# DIY_ST-Link_V21.net
KiCad netlist of a schematic drawn in Altium Designer
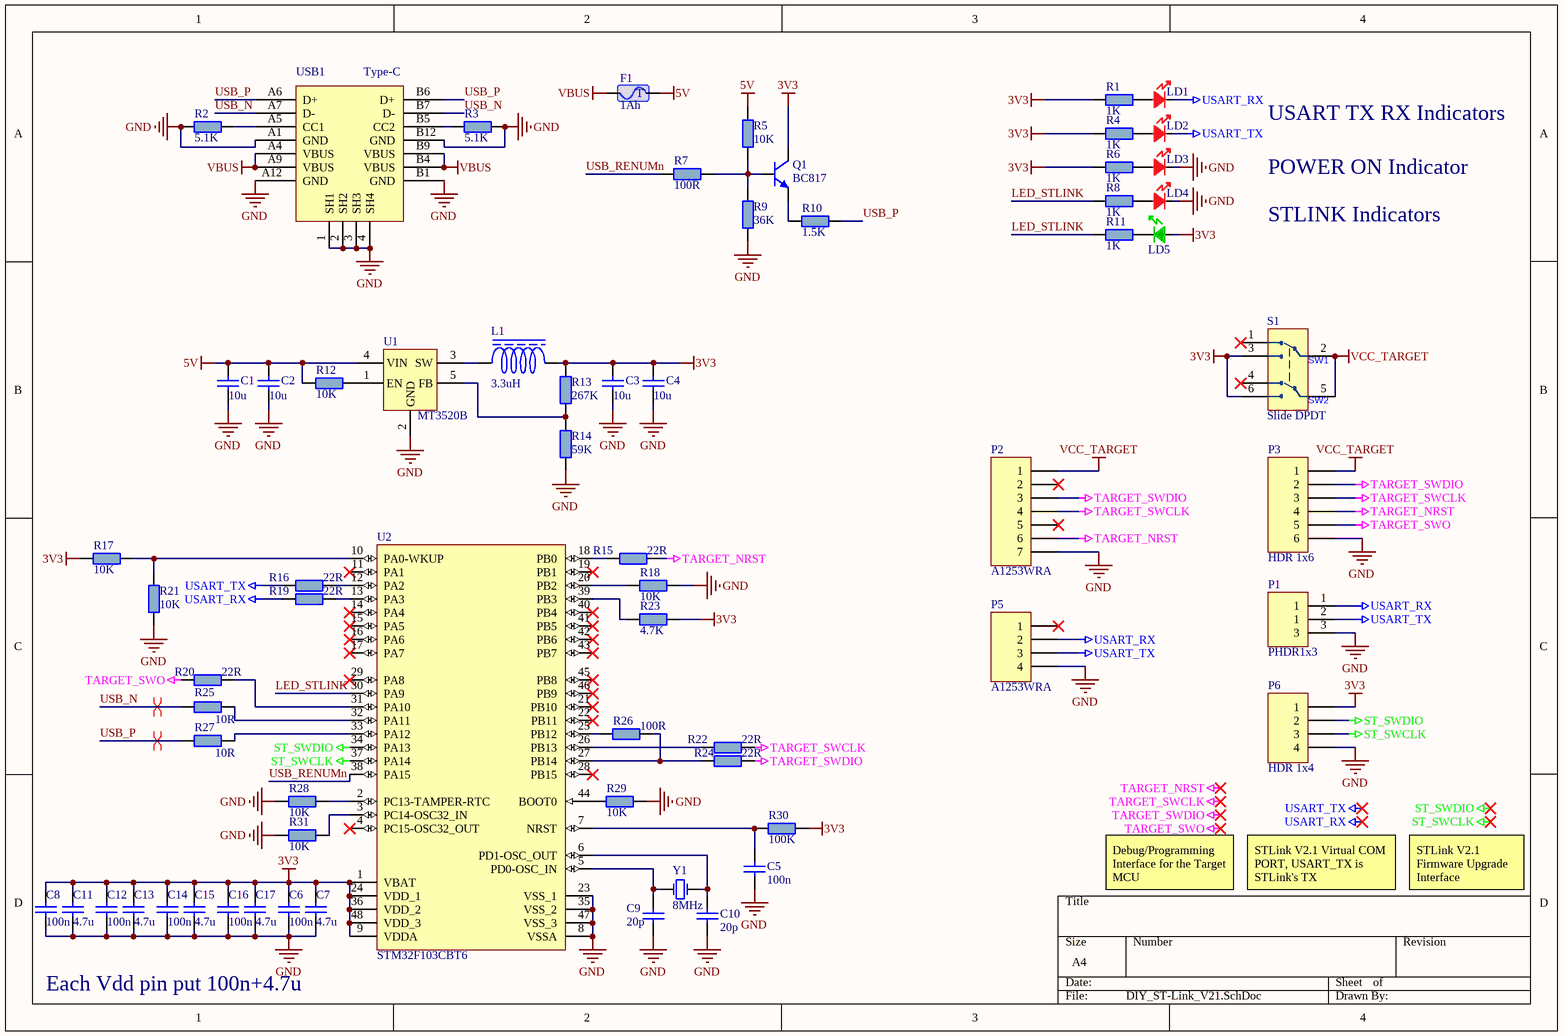
[diagram p0: DIY_ST-Link_V21.SchDoc]

(export (version "E")
  (design (tool "Eeschema 10.0.6"))
  (components
    (comp (ref "C1")
      (value "10u")
      (footprint "0805_CAP")
      (description "Capacitor, Ceramic,, ?F, ?V, 0805")
      (libsource (lib "BC_Schematic Lib SMT") (part "CC_?F_0805"))
    )
    (comp (ref "C2")
      (value "10u")
      (footprint "0805_CAP")
      (description "Capacitor, Ceramic,, ?F, ?V, 0805")
      (libsource (lib "BC_Schematic Lib SMT") (part "CC_?F_0805"))
    )
    (comp (ref "C3")
      (value "10u")
      (footprint "0805_CAP")
      (description "Capacitor, Ceramic,, ?F, ?V, 0805")
      (libsource (lib "BC_Schematic Lib SMT") (part "CC_?F_0805"))
    )
    (comp (ref "C4")
      (value "10u")
      (footprint "0805_CAP")
      (description "Capacitor, Ceramic,, ?F, ?V, 0805")
      (libsource (lib "BC_Schematic Lib SMT") (part "CC_?F_0805"))
    )
    (comp (ref "C5")
      (value "100n")
      (footprint "0805_CAP")
      (description "Capacitor, Ceramic,, ?F, ?V, 0805")
      (libsource (lib "BC_Schematic Lib SMT") (part "CC_?F_0805"))
    )
    (comp (ref "C6")
      (value "100n")
      (footprint "0805_CAP")
      (description "Capacitor, Ceramic,, ?F, ?V, 0805")
      (libsource (lib "BC_Schematic Lib SMT") (part "CC_?F_0805"))
    )
    (comp (ref "C7")
      (value "4.7u")
      (footprint "0805_CAP")
      (description "Capacitor, Ceramic,, ?F, ?V, 0805")
      (libsource (lib "BC_Schematic Lib SMT") (part "CC_?F_0805"))
    )
    (comp (ref "C8")
      (value "100n")
      (footprint "0805_CAP")
      (description "Capacitor, Ceramic,, ?F, ?V, 0805")
      (libsource (lib "BC_Schematic Lib SMT") (part "CC_?F_0805"))
    )
    (comp (ref "C9")
      (value "20p")
      (footprint "0805_CAP")
      (description "Capacitor, Ceramic,, ?F, ?V, 0805")
      (libsource (lib "BC_Schematic Lib SMT") (part "CC_?F_0805"))
    )
    (comp (ref "C10")
      (value "20p")
      (footprint "0805_CAP")
      (description "Capacitor, Ceramic,, ?F, ?V, 0805")
      (libsource (lib "BC_Schematic Lib SMT") (part "CC_?F_0805"))
    )
    (comp (ref "C11")
      (value "4.7u")
      (footprint "0805_CAP")
      (description "Capacitor, Ceramic,, ?F, ?V, 0805")
      (libsource (lib "BC_Schematic Lib SMT") (part "CC_?F_0805"))
    )
    (comp (ref "C12")
      (value "100n")
      (footprint "0805_CAP")
      (description "Capacitor, Ceramic,, ?F, ?V, 0805")
      (libsource (lib "BC_Schematic Lib SMT") (part "CC_?F_0805"))
    )
    (comp (ref "C13")
      (value "4.7u")
      (footprint "0805_CAP")
      (description "Capacitor, Ceramic,, ?F, ?V, 0805")
      (libsource (lib "BC_Schematic Lib SMT") (part "CC_?F_0805"))
    )
    (comp (ref "C14")
      (value "100n")
      (footprint "0805_CAP")
      (description "Capacitor, Ceramic,, ?F, ?V, 0805")
      (libsource (lib "BC_Schematic Lib SMT") (part "CC_?F_0805"))
    )
    (comp (ref "C15")
      (value "4.7u")
      (footprint "0805_CAP")
      (description "Capacitor, Ceramic,, ?F, ?V, 0805")
      (libsource (lib "BC_Schematic Lib SMT") (part "CC_?F_0805"))
    )
    (comp (ref "C16")
      (value "100n")
      (footprint "0805_CAP")
      (description "Capacitor, Ceramic,, ?F, ?V, 0805")
      (libsource (lib "BC_Schematic Lib SMT") (part "CC_?F_0805"))
    )
    (comp (ref "C17")
      (value "4.7u")
      (footprint "0805_CAP")
      (description "Capacitor, Ceramic,, ?F, ?V, 0805")
      (libsource (lib "BC_Schematic Lib SMT") (part "CC_?F_0805"))
    )
    (comp (ref "F1")
      (value "1Ah")
      (footprint "1206_PS")
      (description "Fuse, Polyswitch, 1Ah 1.8At, 6V, 8A @300msec, 210mRmax, 1206 [3216]")
      (libsource (lib "BC_Schematic Lib SMT") (part "Fuse_PS_1A6V_3216"))
    )
    (comp (ref "L1")
      (value "3.3uH")
      (footprint "IND_40x45x3.2")
      (description "https://www.lcsc.com/product-detail/Inductors-SMD_SHOU-HAN-CY43-3-3UH_C2929417.html")
      (libsource (lib "BC_Schematic Lib SMT") (part "IND_?uH_4045"))
    )
    (comp (ref "LD1")
      (value "Red")
      (footprint "LED0805_Red")
      (description "LED, Red, 2.0V, Imax 30mA, 120deg. At 20mA => Wavelength = 630nm, 230mcd, 0805")
      (fields (field (name "MANUFACTURER") "Kingbright"))
      (libsource (lib "BC_Schematic Lib SMT") (part "LED_RED230mcd_2013"))
    )
    (comp (ref "LD2")
      (value "Red")
      (footprint "LED0805_Red")
      (description "LED, Red, 2.0V, Imax 30mA, 120deg. At 20mA => Wavelength = 630nm, 230mcd, 0805")
      (fields (field (name "MANUFACTURER") "Kingbright"))
      (libsource (lib "BC_Schematic Lib SMT") (part "LED_RED230mcd_2013"))
    )
    (comp (ref "LD3")
      (value "Red")
      (footprint "LED0805_Red")
      (description "LED, Red, 2.0V, Imax 30mA, 120deg. At 20mA => Wavelength = 630nm, 230mcd, 0805")
      (fields (field (name "MANUFACTURER") "Kingbright"))
      (libsource (lib "BC_Schematic Lib SMT") (part "LED_RED230mcd_2013"))
    )
    (comp (ref "LD4")
      (value "Red")
      (footprint "LED0805_Red")
      (description "LED, Red, 2.0V, Imax 30mA, 120deg. At 20mA => Wavelength = 630nm, 230mcd, 0805")
      (fields (field (name "MANUFACTURER") "Kingbright"))
      (libsource (lib "BC_Schematic Lib SMT") (part "LED_RED230mcd_2013"))
    )
    (comp (ref "LD5")
      (value "Green")
      (footprint "LED0805_green")
      (description "LED, Green, 2.1V, Imax 30mA, 110deg. At 20mA => Wavelength = 570nm, 50mcd, 0805")
      (fields (field (name "MANUFACTURER") "Kingbright"))
      (libsource (lib "BC_Schematic Lib SMT") (part "LED_GRN50mcd_2013"))
    )
    (comp (ref "P1")
      (value "PHDR1x3")
      (footprint "HEADER_1x3")
      (description "Header, 3 pin SIL, 2.54 pitch")
      (libsource (lib "BC_Schematic Lib") (part "Header1x3"))
    )
    (comp (ref "P2")
      (value "A1253WRA")
      (footprint "A1253WRA-7P")
      (description "A1253WRA-4P")
      (fields (field (name "ENGINEER’S NAME") "WZ"))
      (libsource (lib "BC_Schematic Lib SMT") (part "A1253WRA-7P"))
    )
    (comp (ref "P3")
      (value "HDR 1x6")
      (footprint "HEADER_1x6")
      (description "Header_1x6")
      (libsource (lib "BC_Schematic Lib") (part "Header1x6"))
    )
    (comp (ref "P5")
      (value "A1253WRA")
      (footprint "A1253WRA-4P")
      (description "A1253WRA-4P")
      (fields (field (name "ENGINEER’S NAME") "WZ"))
      (libsource (lib "BC_Schematic Lib SMT") (part "A1253WRA-4P"))
    )
    (comp (ref "P6")
      (value "HDR 1x4")
      (footprint "HEADER_1x4")
      (description "Header_1x4")
      (fields (field (name "ENGINEER’S NAME") "WZ"))
      (libsource (lib "BC_Schematic Lib") (part "Header1x4"))
    )
    (comp (ref "Q1")
      (value "BC817")
      (footprint "SOT23")
      (description "TRANSISTOR, NPN, SOT-23, 45V")
      (fields (field (name "MANUFACTURER") "NXP"))
      (libsource (lib "BC_Schematic Lib SMT") (part "TR_BC817"))
    )
    (comp (ref "R1")
      (value "1K")
      (footprint "0805_res")
      (description "Resistor, ?ohm, 0805")
      (libsource (lib "BC_Schematic Lib SMT") (part "RS_?R_0805"))
    )
    (comp (ref "R2")
      (value "5.1K")
      (footprint "0805_res")
      (description "Resistor, ?ohm, 0805")
      (libsource (lib "") (part "RS_?R_0805_2"))
    )
    (comp (ref "R3")
      (value "5.1K")
      (footprint "0805_res")
      (description "Resistor, ?ohm, 0805")
      (libsource (lib "BC_Schematic Lib SMT") (part "RS_?R_0805"))
    )
    (comp (ref "R4")
      (value "1K")
      (footprint "0805_res")
      (description "Resistor, ?ohm, 0805")
      (libsource (lib "BC_Schematic Lib SMT") (part "RS_?R_0805"))
    )
    (comp (ref "R5")
      (value "10K")
      (footprint "0805_res")
      (description "Resistor, ?ohm, 0805")
      (libsource (lib "") (part "RS_?R_0805_1"))
    )
    (comp (ref "R6")
      (value "1K")
      (footprint "0805_res")
      (description "Resistor, ?ohm, 0805")
      (libsource (lib "BC_Schematic Lib SMT") (part "RS_?R_0805"))
    )
    (comp (ref "R7")
      (value "100R")
      (footprint "0805_res")
      (description "Resistor, ?ohm, 0805")
      (libsource (lib "") (part "RS_?R_0805_2"))
    )
    (comp (ref "R8")
      (value "1K")
      (footprint "0805_res")
      (description "Resistor, ?ohm, 0805")
      (libsource (lib "BC_Schematic Lib SMT") (part "RS_?R_0805"))
    )
    (comp (ref "R9")
      (value "36K")
      (footprint "0805_res")
      (description "Resistor, ?ohm, 0805")
      (libsource (lib "") (part "RS_?R_0805_1"))
    )
    (comp (ref "R10")
      (value "1.5K")
      (footprint "0805_res")
      (description "Resistor, ?ohm, 0805")
      (libsource (lib "") (part "RS_?R_0805_2"))
    )
    (comp (ref "R11")
      (value "1K")
      (footprint "0805_res")
      (description "Resistor, ?ohm, 0805")
      (libsource (lib "BC_Schematic Lib SMT") (part "RS_?R_0805"))
    )
    (comp (ref "R12")
      (value "10K")
      (footprint "0805_res")
      (description "Resistor, ?ohm, 0805")
      (libsource (lib "BC_Schematic Lib SMT") (part "RS_?R_0805"))
    )
    (comp (ref "R13")
      (value "267K")
      (footprint "0805_res")
      (description "Resistor, ?ohm, 0805")
      (libsource (lib "") (part "RS_?R_0805_3"))
    )
    (comp (ref "R14")
      (value "59K")
      (footprint "0805_res")
      (description "Resistor, ?ohm, 0805")
      (libsource (lib "") (part "RS_?R_0805_3"))
    )
    (comp (ref "R15")
      (value "22R")
      (footprint "0805_res")
      (description "Resistor, ?ohm, 0805")
      (libsource (lib "BC_Schematic Lib SMT") (part "RS_?R_0805"))
    )
    (comp (ref "R16")
      (value "22R")
      (footprint "0805_res")
      (description "Resistor, ?ohm, 0805")
      (libsource (lib "BC_Schematic Lib SMT") (part "RS_?R_0805"))
    )
    (comp (ref "R17")
      (value "10K")
      (footprint "0805_res")
      (description "Resistor, ?ohm, 0805")
      (libsource (lib "BC_Schematic Lib SMT") (part "RS_?R_0805"))
    )
    (comp (ref "R18")
      (value "10K")
      (footprint "0805_res")
      (description "Resistor, ?ohm, 0805")
      (libsource (lib "BC_Schematic Lib SMT") (part "RS_?R_0805"))
    )
    (comp (ref "R19")
      (value "22R")
      (footprint "0805_res")
      (description "Resistor, ?ohm, 0805")
      (libsource (lib "BC_Schematic Lib SMT") (part "RS_?R_0805"))
    )
    (comp (ref "R20")
      (value "22R")
      (footprint "0805_res")
      (description "Resistor, ?ohm, 0805")
      (libsource (lib "BC_Schematic Lib SMT") (part "RS_?R_0805"))
    )
    (comp (ref "R21")
      (value "10K")
      (footprint "0805_res")
      (description "Resistor, ?ohm, 0805")
      (libsource (lib "") (part "RS_?R_0805_1"))
    )
    (comp (ref "R22")
      (value "22R")
      (footprint "0805_res")
      (description "Resistor, ?ohm, 0805")
      (libsource (lib "BC_Schematic Lib SMT") (part "RS_?R_0805"))
    )
    (comp (ref "R23")
      (value "4.7K")
      (footprint "0805_res")
      (description "Resistor, ?ohm, 0805")
      (libsource (lib "BC_Schematic Lib SMT") (part "RS_?R_0805"))
    )
    (comp (ref "R24")
      (value "22R")
      (footprint "0805_res")
      (description "Resistor, ?ohm, 0805")
      (libsource (lib "BC_Schematic Lib SMT") (part "RS_?R_0805"))
    )
    (comp (ref "R25")
      (value "10R")
      (footprint "0805_res")
      (description "Resistor, ?ohm, 0805")
      (libsource (lib "BC_Schematic Lib SMT") (part "RS_?R_0805"))
    )
    (comp (ref "R26")
      (value "100R")
      (footprint "0805_res")
      (description "Resistor, ?ohm, 0805")
      (libsource (lib "BC_Schematic Lib SMT") (part "RS_?R_0805"))
    )
    (comp (ref "R27")
      (value "10R")
      (footprint "0805_res")
      (description "Resistor, ?ohm, 0805")
      (libsource (lib "BC_Schematic Lib SMT") (part "RS_?R_0805"))
    )
    (comp (ref "R28")
      (value "10K")
      (footprint "0805_res")
      (description "Resistor, ?ohm, 0805")
      (libsource (lib "BC_Schematic Lib SMT") (part "RS_?R_0805"))
    )
    (comp (ref "R29")
      (value "10K")
      (footprint "0805_res")
      (description "Resistor, ?ohm, 0805")
      (libsource (lib "BC_Schematic Lib SMT") (part "RS_?R_0805"))
    )
    (comp (ref "R30")
      (value "100K")
      (footprint "0805_res")
      (description "Resistor, ?ohm, 0805")
      (libsource (lib "BC_Schematic Lib SMT") (part "RS_?R_0805"))
    )
    (comp (ref "R31")
      (value "10K")
      (footprint "0805_res")
      (description "Resistor, ?ohm, 0805")
      (libsource (lib "BC_Schematic Lib SMT") (part "RS_?R_0805"))
    )
    (comp (ref "S1")
      (value "Slide DPDT")
      (footprint "SW_DPDT_SMD")
      (libsource (lib "BC_Schematic Lib SMT") (part "SW_Slide_DPDT"))
    )
    (comp (ref "U1")
      (value "MT3520B")
      (footprint "SOT23-5")
      (description "https://www.lcsc.com/product-detail/DC-DC-Converters_XI-AN-Aerosemi-Tech-MT3520B_C2684933.html")
      (libsource (lib "BC_Schematic Lib SMT") (part "BUCK_MT3520B"))
    )
    (comp (ref "U2")
      (value "STM32F103CBT6")
      (footprint "LQFP-48")
      (libsource (lib "BC_Schematic Lib SMT") (part "STM32F103CBT6"))
    )
    (comp (ref "USB1")
      (value "Type-C")
      (footprint "Type-C-TOP")
      (libsource (lib "BC_Schematic Lib SMT") (part "USB-Type-C-TOP"))
    )
    (comp (ref "Y1")
      (value "8MHz")
      (footprint "Xtal_HC49_US")
      (description "Crystal, SMD, HC49 Size")
      (fields (field (name "MANUFACTURER") "Abracon Corporation"))
      (libsource (lib "BC_Schematic Lib SMT") (part "XTAL-SMD_HC49"))
    )
  )
  (nets
    (net (code "1") (name "/LED_STLINK") (class "Default")
      (node (ref "R11") (pin "2") (pinfunction "2_2") (pintype "passive"))
      (node (ref "R8") (pin "2") (pinfunction "2_2") (pintype "passive"))
      (node (ref "U2") (pin "30") (pinfunction "PA9_30") (pintype "bidirectional"))
    )
    (net (code "2") (name "/USB_N") (class "Default")
      (node (ref "R25") (pin "2") (pinfunction "2_2") (pintype "passive"))
      (node (ref "USB1") (pin "A7") (pinfunction "D-_A7") (pintype "passive"))
      (node (ref "USB1") (pin "B7") (pinfunction "D-_B7") (pintype "passive"))
    )
    (net (code "3") (name "/USB_P") (class "Default")
      (node (ref "R10") (pin "2") (pinfunction "2_2") (pintype "passive"))
      (node (ref "R27") (pin "2") (pinfunction "2_2") (pintype "passive"))
      (node (ref "USB1") (pin "A6") (pinfunction "D+_A6") (pintype "passive"))
      (node (ref "USB1") (pin "B6") (pinfunction "D+_B6") (pintype "passive"))
    )
    (net (code "4") (name "/USB_RENUMn") (class "Default")
      (node (ref "R7") (pin "1") (pinfunction "1_1") (pintype "passive"))
      (node (ref "U2") (pin "38") (pinfunction "PA15_38") (pintype "bidirectional"))
    )
    (net (code "5") (name "3V3") (class "Default")
      (node (ref "C11") (pin "2") (pinfunction "2_2") (pintype "passive"))
      (node (ref "C12") (pin "2") (pinfunction "2_2") (pintype "passive"))
      (node (ref "C13") (pin "2") (pinfunction "2_2") (pintype "passive"))
      (node (ref "C14") (pin "2") (pinfunction "2_2") (pintype "passive"))
      (node (ref "C15") (pin "2") (pinfunction "2_2") (pintype "passive"))
      (node (ref "C16") (pin "2") (pinfunction "2_2") (pintype "passive"))
      (node (ref "C17") (pin "2") (pinfunction "2_2") (pintype "passive"))
      (node (ref "C3") (pin "2") (pinfunction "2_2") (pintype "passive"))
      (node (ref "C4") (pin "2") (pinfunction "2_2") (pintype "passive"))
      (node (ref "C6") (pin "2") (pinfunction "2_2") (pintype "passive"))
      (node (ref "C7") (pin "2") (pinfunction "2_2") (pintype "passive"))
      (node (ref "C8") (pin "2") (pinfunction "2_2") (pintype "passive"))
      (node (ref "L1") (pin "2") (pinfunction "2_2") (pintype "passive"))
      (node (ref "LD5") (pin "1") (pinfunction "A_1") (pintype "passive"))
      (node (ref "P6") (pin "1") (pinfunction "1_1") (pintype "passive"))
      (node (ref "Q1") (pin "3") (pinfunction "C_3") (pintype "passive"))
      (node (ref "R1") (pin "2") (pinfunction "2_2") (pintype "passive"))
      (node (ref "R13") (pin "1") (pinfunction "1_1") (pintype "passive"))
      (node (ref "R17") (pin "2") (pinfunction "2_2") (pintype "passive"))
      (node (ref "R23") (pin "1") (pinfunction "1_1") (pintype "passive"))
      (node (ref "R30") (pin "1") (pinfunction "1_1") (pintype "passive"))
      (node (ref "R4") (pin "2") (pinfunction "2_2") (pintype "passive"))
      (node (ref "R6") (pin "2") (pinfunction "2_2") (pintype "passive"))
      (node (ref "S1") (pin "3") (pinfunction "NO1_3") (pintype "passive"))
      (node (ref "S1") (pin "6") (pinfunction "NO2_6") (pintype "passive"))
      (node (ref "U2") (pin "1") (pinfunction "VBAT_1") (pintype "power_in"))
      (node (ref "U2") (pin "24") (pinfunction "VDD_1_24") (pintype "power_in"))
      (node (ref "U2") (pin "36") (pinfunction "VDD_2_36") (pintype "power_in"))
      (node (ref "U2") (pin "48") (pinfunction "VDD_3_48") (pintype "power_in"))
      (node (ref "U2") (pin "9") (pinfunction "VDDA_9") (pintype "power_in"))
    )
    (net (code "6") (name "5V") (class "Default")
      (node (ref "C1") (pin "2") (pinfunction "2_2") (pintype "passive"))
      (node (ref "C2") (pin "2") (pinfunction "2_2") (pintype "passive"))
      (node (ref "F1") (pin "2") (pinfunction "2_2") (pintype "passive"))
      (node (ref "R12") (pin "2") (pinfunction "2_2") (pintype "passive"))
      (node (ref "R5") (pin "2") (pinfunction "2_2") (pintype "passive"))
      (node (ref "U1") (pin "4") (pinfunction "VIN_4") (pintype "passive"))
    )
    (net (code "7") (name "GND") (class "Default")
      (node (ref "C1") (pin "1") (pinfunction "1_1") (pintype "passive"))
      (node (ref "C10") (pin "1") (pinfunction "1_1") (pintype "passive"))
      (node (ref "C11") (pin "1") (pinfunction "1_1") (pintype "passive"))
      (node (ref "C12") (pin "1") (pinfunction "1_1") (pintype "passive"))
      (node (ref "C13") (pin "1") (pinfunction "1_1") (pintype "passive"))
      (node (ref "C14") (pin "1") (pinfunction "1_1") (pintype "passive"))
      (node (ref "C15") (pin "1") (pinfunction "1_1") (pintype "passive"))
      (node (ref "C16") (pin "1") (pinfunction "1_1") (pintype "passive"))
      (node (ref "C17") (pin "1") (pinfunction "1_1") (pintype "passive"))
      (node (ref "C2") (pin "1") (pinfunction "1_1") (pintype "passive"))
      (node (ref "C3") (pin "1") (pinfunction "1_1") (pintype "passive"))
      (node (ref "C4") (pin "1") (pinfunction "1_1") (pintype "passive"))
      (node (ref "C5") (pin "1") (pinfunction "1_1") (pintype "passive"))
      (node (ref "C6") (pin "1") (pinfunction "1_1") (pintype "passive"))
      (node (ref "C7") (pin "1") (pinfunction "1_1") (pintype "passive"))
      (node (ref "C8") (pin "1") (pinfunction "1_1") (pintype "passive"))
      (node (ref "C9") (pin "1") (pinfunction "1_1") (pintype "passive"))
      (node (ref "LD3") (pin "2") (pinfunction "K_2") (pintype "passive"))
      (node (ref "LD4") (pin "2") (pinfunction "K_2") (pintype "passive"))
      (node (ref "P1") (pin "3") (pinfunction "3_3") (pintype "passive"))
      (node (ref "P2") (pin "7") (pinfunction "7_7") (pintype "passive"))
      (node (ref "P3") (pin "6") (pinfunction "6_6") (pintype "passive"))
      (node (ref "P5") (pin "4") (pinfunction "4_4") (pintype "passive"))
      (node (ref "P6") (pin "4") (pinfunction "4_4") (pintype "passive"))
      (node (ref "R14") (pin "2") (pinfunction "2_2") (pintype "passive"))
      (node (ref "R18") (pin "1") (pinfunction "1_1") (pintype "passive"))
      (node (ref "R2") (pin "1") (pinfunction "1_1") (pintype "passive"))
      (node (ref "R21") (pin "1") (pinfunction "1_1") (pintype "passive"))
      (node (ref "R28") (pin "2") (pinfunction "2_2") (pintype "passive"))
      (node (ref "R29") (pin "1") (pinfunction "1_1") (pintype "passive"))
      (node (ref "R3") (pin "1") (pinfunction "1_1") (pintype "passive"))
      (node (ref "R31") (pin "2") (pinfunction "2_2") (pintype "passive"))
      (node (ref "R9") (pin "1") (pinfunction "1_1") (pintype "passive"))
      (node (ref "U1") (pin "2") (pinfunction "GND_2") (pintype "passive"))
      (node (ref "U2") (pin "23") (pinfunction "VSS_1_23") (pintype "power_in"))
      (node (ref "U2") (pin "35") (pinfunction "VSS_2_35") (pintype "power_in"))
      (node (ref "U2") (pin "47") (pinfunction "VSS_3_47") (pintype "power_in"))
      (node (ref "U2") (pin "8") (pinfunction "VSSA_8") (pintype "power_in"))
      (node (ref "USB1") (pin "1") (pinfunction "SH1_1") (pintype "passive"))
      (node (ref "USB1") (pin "2") (pinfunction "SH2_2") (pintype "passive"))
      (node (ref "USB1") (pin "3") (pinfunction "SH3_3") (pintype "passive"))
      (node (ref "USB1") (pin "4") (pinfunction "SH4_4") (pintype "passive"))
      (node (ref "USB1") (pin "A1") (pinfunction "GND_A1") (pintype "passive"))
      (node (ref "USB1") (pin "A12") (pinfunction "GND_A12") (pintype "passive"))
      (node (ref "USB1") (pin "B1") (pinfunction "GND_B1") (pintype "passive"))
      (node (ref "USB1") (pin "B12") (pinfunction "GND_B12") (pintype "passive"))
    )
    (net (code "8") (name "Net-(LD1-A)") (class "Default")
      (node (ref "LD1") (pin "1") (pinfunction "A_1") (pintype "passive"))
      (node (ref "R1") (pin "1") (pinfunction "1_1") (pintype "passive"))
    )
    (net (code "9") (name "Net-(LD2-A)") (class "Default")
      (node (ref "LD2") (pin "1") (pinfunction "A_1") (pintype "passive"))
      (node (ref "R4") (pin "1") (pinfunction "1_1") (pintype "passive"))
    )
    (net (code "10") (name "Net-(LD3-A)") (class "Default")
      (node (ref "LD3") (pin "1") (pinfunction "A_1") (pintype "passive"))
      (node (ref "R6") (pin "1") (pinfunction "1_1") (pintype "passive"))
    )
    (net (code "11") (name "Net-(LD4-A)") (class "Default")
      (node (ref "LD4") (pin "1") (pinfunction "A_1") (pintype "passive"))
      (node (ref "R8") (pin "1") (pinfunction "1_1") (pintype "passive"))
    )
    (net (code "12") (name "Net-(LD5-K)") (class "Default")
      (node (ref "LD5") (pin "2") (pinfunction "K_2") (pintype "passive"))
      (node (ref "R11") (pin "1") (pinfunction "1_1") (pintype "passive"))
    )
    (net (code "13") (name "Net-(Q1-B)") (class "Default")
      (node (ref "Q1") (pin "1") (pinfunction "B_1") (pintype "passive"))
      (node (ref "R5") (pin "1") (pinfunction "1_1") (pintype "passive"))
      (node (ref "R7") (pin "2") (pinfunction "2_2") (pintype "passive"))
      (node (ref "R9") (pin "2") (pinfunction "2_2") (pintype "passive"))
    )
    (net (code "14") (name "Net-(Q1-E)") (class "Default")
      (node (ref "Q1") (pin "2") (pinfunction "E_2") (pintype "passive"))
      (node (ref "R10") (pin "1") (pinfunction "1_1") (pintype "passive"))
    )
    (net (code "15") (name "Net-(U1-EN)") (class "Default")
      (node (ref "R12") (pin "1") (pinfunction "1_1") (pintype "passive"))
      (node (ref "U1") (pin "1") (pinfunction "EN_1") (pintype "passive"))
    )
    (net (code "16") (name "Net-(U1-FB)") (class "Default")
      (node (ref "R13") (pin "2") (pinfunction "2_2") (pintype "passive"))
      (node (ref "R14") (pin "1") (pinfunction "1_1") (pintype "passive"))
      (node (ref "U1") (pin "5") (pinfunction "FB_5") (pintype "passive"))
    )
    (net (code "17") (name "Net-(U1-SW)") (class "Default")
      (node (ref "L1") (pin "1") (pinfunction "1_1") (pintype "passive"))
      (node (ref "U1") (pin "3") (pinfunction "SW_3") (pintype "passive"))
    )
    (net (code "18") (name "Net-(U2-BOOT0)") (class "Default")
      (node (ref "R29") (pin "2") (pinfunction "2_2") (pintype "passive"))
      (node (ref "U2") (pin "44") (pinfunction "BOOT0_44") (pintype "input"))
    )
    (net (code "19") (name "Net-(U2-NRST)") (class "Default")
      (node (ref "C5") (pin "2") (pinfunction "2_2") (pintype "passive"))
      (node (ref "R30") (pin "2") (pinfunction "2_2") (pintype "passive"))
      (node (ref "U2") (pin "7") (pinfunction "NRST_7") (pintype "bidirectional"))
    )
    (net (code "20") (name "Net-(U2-PA0-WKUP)") (class "Default")
      (node (ref "R17") (pin "1") (pinfunction "1_1") (pintype "passive"))
      (node (ref "R21") (pin "2") (pinfunction "2_2") (pintype "passive"))
      (node (ref "U2") (pin "10") (pinfunction "PA0-WKUP_10") (pintype "bidirectional"))
    )
    (net (code "21") (name "Net-(U2-PA2)") (class "Default")
      (node (ref "R16") (pin "1") (pinfunction "1_1") (pintype "passive"))
      (node (ref "U2") (pin "12") (pinfunction "PA2_12") (pintype "bidirectional"))
    )
    (net (code "22") (name "Net-(U2-PA3)") (class "Default")
      (node (ref "R19") (pin "1") (pinfunction "1_1") (pintype "passive"))
      (node (ref "U2") (pin "13") (pinfunction "PA3_13") (pintype "bidirectional"))
    )
    (net (code "23") (name "Net-(U2-PA10)") (class "Default")
      (node (ref "R20") (pin "1") (pinfunction "1_1") (pintype "passive"))
      (node (ref "U2") (pin "31") (pinfunction "PA10_31") (pintype "bidirectional"))
    )
    (net (code "24") (name "Net-(U2-PA11)") (class "Default")
      (node (ref "R25") (pin "1") (pinfunction "1_1") (pintype "passive"))
      (node (ref "U2") (pin "32") (pinfunction "PA11_32") (pintype "bidirectional"))
    )
    (net (code "25") (name "Net-(U2-PA12)") (class "Default")
      (node (ref "R27") (pin "1") (pinfunction "1_1") (pintype "passive"))
      (node (ref "U2") (pin "33") (pinfunction "PA12_33") (pintype "bidirectional"))
    )
    (net (code "26") (name "Net-(U2-PB0)") (class "Default")
      (node (ref "R15") (pin "2") (pinfunction "2_2") (pintype "passive"))
      (node (ref "U2") (pin "18") (pinfunction "PB0_18") (pintype "bidirectional"))
    )
    (net (code "27") (name "Net-(U2-PB2)") (class "Default")
      (node (ref "R18") (pin "2") (pinfunction "2_2") (pintype "passive"))
      (node (ref "U2") (pin "20") (pinfunction "PB2_20") (pintype "bidirectional"))
    )
    (net (code "28") (name "Net-(U2-PB3)") (class "Default")
      (node (ref "R23") (pin "2") (pinfunction "2_2") (pintype "passive"))
      (node (ref "U2") (pin "39") (pinfunction "PB3_39") (pintype "bidirectional"))
    )
    (net (code "29") (name "Net-(U2-PB12)") (class "Default")
      (node (ref "R26") (pin "2") (pinfunction "2_2") (pintype "passive"))
      (node (ref "U2") (pin "25") (pinfunction "PB12_25") (pintype "bidirectional"))
    )
    (net (code "30") (name "Net-(U2-PB13)") (class "Default")
      (node (ref "R22") (pin "2") (pinfunction "2_2") (pintype "passive"))
      (node (ref "U2") (pin "26") (pinfunction "PB13_26") (pintype "bidirectional"))
    )
    (net (code "31") (name "Net-(U2-PB14)") (class "Default")
      (node (ref "R24") (pin "2") (pinfunction "2_2") (pintype "passive"))
      (node (ref "R26") (pin "1") (pinfunction "1_1") (pintype "passive"))
      (node (ref "U2") (pin "27") (pinfunction "PB14_27") (pintype "bidirectional"))
    )
    (net (code "32") (name "Net-(U2-PC13-TAMPER-RTC)") (class "Default")
      (node (ref "R28") (pin "1") (pinfunction "1_1") (pintype "passive"))
      (node (ref "U2") (pin "2") (pinfunction "PC13-TAMPER-RTC_2") (pintype "bidirectional"))
    )
    (net (code "33") (name "Net-(U2-PC14-OSC32_IN)") (class "Default")
      (node (ref "R31") (pin "1") (pinfunction "1_1") (pintype "passive"))
      (node (ref "U2") (pin "3") (pinfunction "PC14-OSC32_IN_3") (pintype "bidirectional"))
    )
    (net (code "34") (name "Net-(U2-PD0-OSC_IN)") (class "Default")
      (node (ref "C9") (pin "2") (pinfunction "2_2") (pintype "passive"))
      (node (ref "U2") (pin "5") (pinfunction "PD0-OSC_IN_5") (pintype "bidirectional"))
      (node (ref "Y1") (pin "1") (pinfunction "OSC1_1") (pintype "passive"))
    )
    (net (code "35") (name "Net-(U2-PD1-OSC_OUT)") (class "Default")
      (node (ref "C10") (pin "2") (pinfunction "2_2") (pintype "passive"))
      (node (ref "U2") (pin "6") (pinfunction "PD1-OSC_OUT_6") (pintype "bidirectional"))
      (node (ref "Y1") (pin "2") (pinfunction "OSC2_2") (pintype "passive"))
    )
    (net (code "36") (name "Net-(USB1-CC1)") (class "Default")
      (node (ref "R2") (pin "2") (pinfunction "2_2") (pintype "passive"))
      (node (ref "USB1") (pin "A5") (pinfunction "CC1_A5") (pintype "passive"))
    )
    (net (code "37") (name "Net-(USB1-CC2)") (class "Default")
      (node (ref "R3") (pin "2") (pinfunction "2_2") (pintype "passive"))
      (node (ref "USB1") (pin "B5") (pinfunction "CC2_B5") (pintype "passive"))
    )
    (net (code "38") (name "ST_SWCLK") (class "Default")
      (node (ref "P6") (pin "3") (pinfunction "3_3") (pintype "passive"))
      (node (ref "U2") (pin "37") (pinfunction "PA14_37") (pintype "bidirectional"))
    )
    (net (code "39") (name "ST_SWDIO") (class "Default")
      (node (ref "P6") (pin "2") (pinfunction "2_2") (pintype "passive"))
      (node (ref "U2") (pin "34") (pinfunction "PA13_34") (pintype "bidirectional"))
    )
    (net (code "40") (name "TARGET_NRST") (class "Default")
      (node (ref "P2") (pin "6") (pinfunction "6_6") (pintype "passive"))
      (node (ref "P3") (pin "4") (pinfunction "4_4") (pintype "passive"))
      (node (ref "R15") (pin "1") (pinfunction "1_1") (pintype "passive"))
    )
    (net (code "41") (name "TARGET_SWCLK") (class "Default")
      (node (ref "P2") (pin "4") (pinfunction "4_4") (pintype "passive"))
      (node (ref "P3") (pin "3") (pinfunction "3_3") (pintype "passive"))
      (node (ref "R22") (pin "1") (pinfunction "1_1") (pintype "passive"))
    )
    (net (code "42") (name "TARGET_SWDIO") (class "Default")
      (node (ref "P2") (pin "3") (pinfunction "3_3") (pintype "passive"))
      (node (ref "P3") (pin "2") (pinfunction "2_2") (pintype "passive"))
      (node (ref "R24") (pin "1") (pinfunction "1_1") (pintype "passive"))
    )
    (net (code "43") (name "TARGET_SWO") (class "Default")
      (node (ref "P3") (pin "5") (pinfunction "5_5") (pintype "passive"))
      (node (ref "R20") (pin "2") (pinfunction "2_2") (pintype "passive"))
    )
    (net (code "44") (name "USART_RX") (class "Default")
      (node (ref "LD1") (pin "2") (pinfunction "K_2") (pintype "passive"))
      (node (ref "P1") (pin "1") (pinfunction "1_1") (pintype "passive"))
      (node (ref "P5") (pin "2") (pinfunction "2_2") (pintype "passive"))
      (node (ref "R19") (pin "2") (pinfunction "2_2") (pintype "passive"))
    )
    (net (code "45") (name "USART_TX") (class "Default")
      (node (ref "LD2") (pin "2") (pinfunction "K_2") (pintype "passive"))
      (node (ref "P1") (pin "2") (pinfunction "1_2") (pintype "passive"))
      (node (ref "P5") (pin "3") (pinfunction "3_3") (pintype "passive"))
      (node (ref "R16") (pin "2") (pinfunction "2_2") (pintype "passive"))
    )
    (net (code "46") (name "VBUS") (class "Default")
      (node (ref "F1") (pin "1") (pinfunction "1_1") (pintype "passive"))
      (node (ref "USB1") (pin "A4") (pinfunction "VBUS_A4") (pintype "passive"))
      (node (ref "USB1") (pin "A9") (pinfunction "VBUS_A9") (pintype "passive"))
      (node (ref "USB1") (pin "B4") (pinfunction "VBUS_B4") (pintype "passive"))
      (node (ref "USB1") (pin "B9") (pinfunction "VBUS_B9") (pintype "passive"))
    )
    (net (code "47") (name "VCC_TARGET") (class "Default")
      (node (ref "P2") (pin "1") (pinfunction "1_1") (pintype "passive"))
      (node (ref "P3") (pin "1") (pinfunction "1_1") (pintype "passive"))
      (node (ref "S1") (pin "2") (pinfunction "C1_2") (pintype "passive"))
      (node (ref "S1") (pin "5") (pinfunction "C2_5") (pintype "passive"))
    )
    (net (code "48") (name "unconnected-(P2-Pad2)") (class "Default")
      (node (ref "P2") (pin "2") (pinfunction "2_2") (pintype "passive+no_connect"))
    )
    (net (code "49") (name "unconnected-(P2-Pad5)") (class "Default")
      (node (ref "P2") (pin "5") (pinfunction "5_5") (pintype "passive+no_connect"))
    )
    (net (code "50") (name "unconnected-(P5-Pad1)") (class "Default")
      (node (ref "P5") (pin "1") (pinfunction "1_1") (pintype "passive+no_connect"))
    )
    (net (code "51") (name "unconnected-(S1-NC1-Pad1)") (class "Default")
      (node (ref "S1") (pin "1") (pinfunction "NC1_1") (pintype "passive+no_connect"))
    )
    (net (code "52") (name "unconnected-(S1-NC2-Pad4)") (class "Default")
      (node (ref "S1") (pin "4") (pinfunction "NC2_4") (pintype "passive+no_connect"))
    )
    (net (code "53") (name "unconnected-(U2-PA1-Pad11)") (class "Default")
      (node (ref "U2") (pin "11") (pinfunction "PA1_11") (pintype "bidirectional+no_connect"))
    )
    (net (code "54") (name "unconnected-(U2-PA4-Pad14)") (class "Default")
      (node (ref "U2") (pin "14") (pinfunction "PA4_14") (pintype "bidirectional+no_connect"))
    )
    (net (code "55") (name "unconnected-(U2-PA5-Pad15)") (class "Default")
      (node (ref "U2") (pin "15") (pinfunction "PA5_15") (pintype "bidirectional+no_connect"))
    )
    (net (code "56") (name "unconnected-(U2-PA6-Pad16)") (class "Default")
      (node (ref "U2") (pin "16") (pinfunction "PA6_16") (pintype "bidirectional+no_connect"))
    )
    (net (code "57") (name "unconnected-(U2-PA7-Pad17)") (class "Default")
      (node (ref "U2") (pin "17") (pinfunction "PA7_17") (pintype "bidirectional+no_connect"))
    )
    (net (code "58") (name "unconnected-(U2-PA8-Pad29)") (class "Default")
      (node (ref "U2") (pin "29") (pinfunction "PA8_29") (pintype "bidirectional+no_connect"))
    )
    (net (code "59") (name "unconnected-(U2-PB1-Pad19)") (class "Default")
      (node (ref "U2") (pin "19") (pinfunction "PB1_19") (pintype "bidirectional+no_connect"))
    )
    (net (code "60") (name "unconnected-(U2-PB4-Pad40)") (class "Default")
      (node (ref "U2") (pin "40") (pinfunction "PB4_40") (pintype "bidirectional+no_connect"))
    )
    (net (code "61") (name "unconnected-(U2-PB5-Pad41)") (class "Default")
      (node (ref "U2") (pin "41") (pinfunction "PB5_41") (pintype "bidirectional+no_connect"))
    )
    (net (code "62") (name "unconnected-(U2-PB6-Pad42)") (class "Default")
      (node (ref "U2") (pin "42") (pinfunction "PB6_42") (pintype "bidirectional+no_connect"))
    )
    (net (code "63") (name "unconnected-(U2-PB7-Pad43)") (class "Default")
      (node (ref "U2") (pin "43") (pinfunction "PB7_43") (pintype "bidirectional+no_connect"))
    )
    (net (code "64") (name "unconnected-(U2-PB8-Pad45)") (class "Default")
      (node (ref "U2") (pin "45") (pinfunction "PB8_45") (pintype "bidirectional+no_connect"))
    )
    (net (code "65") (name "unconnected-(U2-PB9-Pad46)") (class "Default")
      (node (ref "U2") (pin "46") (pinfunction "PB9_46") (pintype "bidirectional+no_connect"))
    )
    (net (code "66") (name "unconnected-(U2-PB10-Pad21)") (class "Default")
      (node (ref "U2") (pin "21") (pinfunction "PB10_21") (pintype "bidirectional+no_connect"))
    )
    (net (code "67") (name "unconnected-(U2-PB11-Pad22)") (class "Default")
      (node (ref "U2") (pin "22") (pinfunction "PB11_22") (pintype "bidirectional+no_connect"))
    )
    (net (code "68") (name "unconnected-(U2-PB15-Pad28)") (class "Default")
      (node (ref "U2") (pin "28") (pinfunction "PB15_28") (pintype "bidirectional+no_connect"))
    )
    (net (code "69") (name "unconnected-(U2-PC15-OSC32_OUT-Pad4)") (class "Default")
      (node (ref "U2") (pin "4") (pinfunction "PC15-OSC32_OUT_4") (pintype "bidirectional+no_connect"))
    )
  )
)
